# E3-LED_1_3.net
KiCad netlist of a schematic drawn in EAGLE
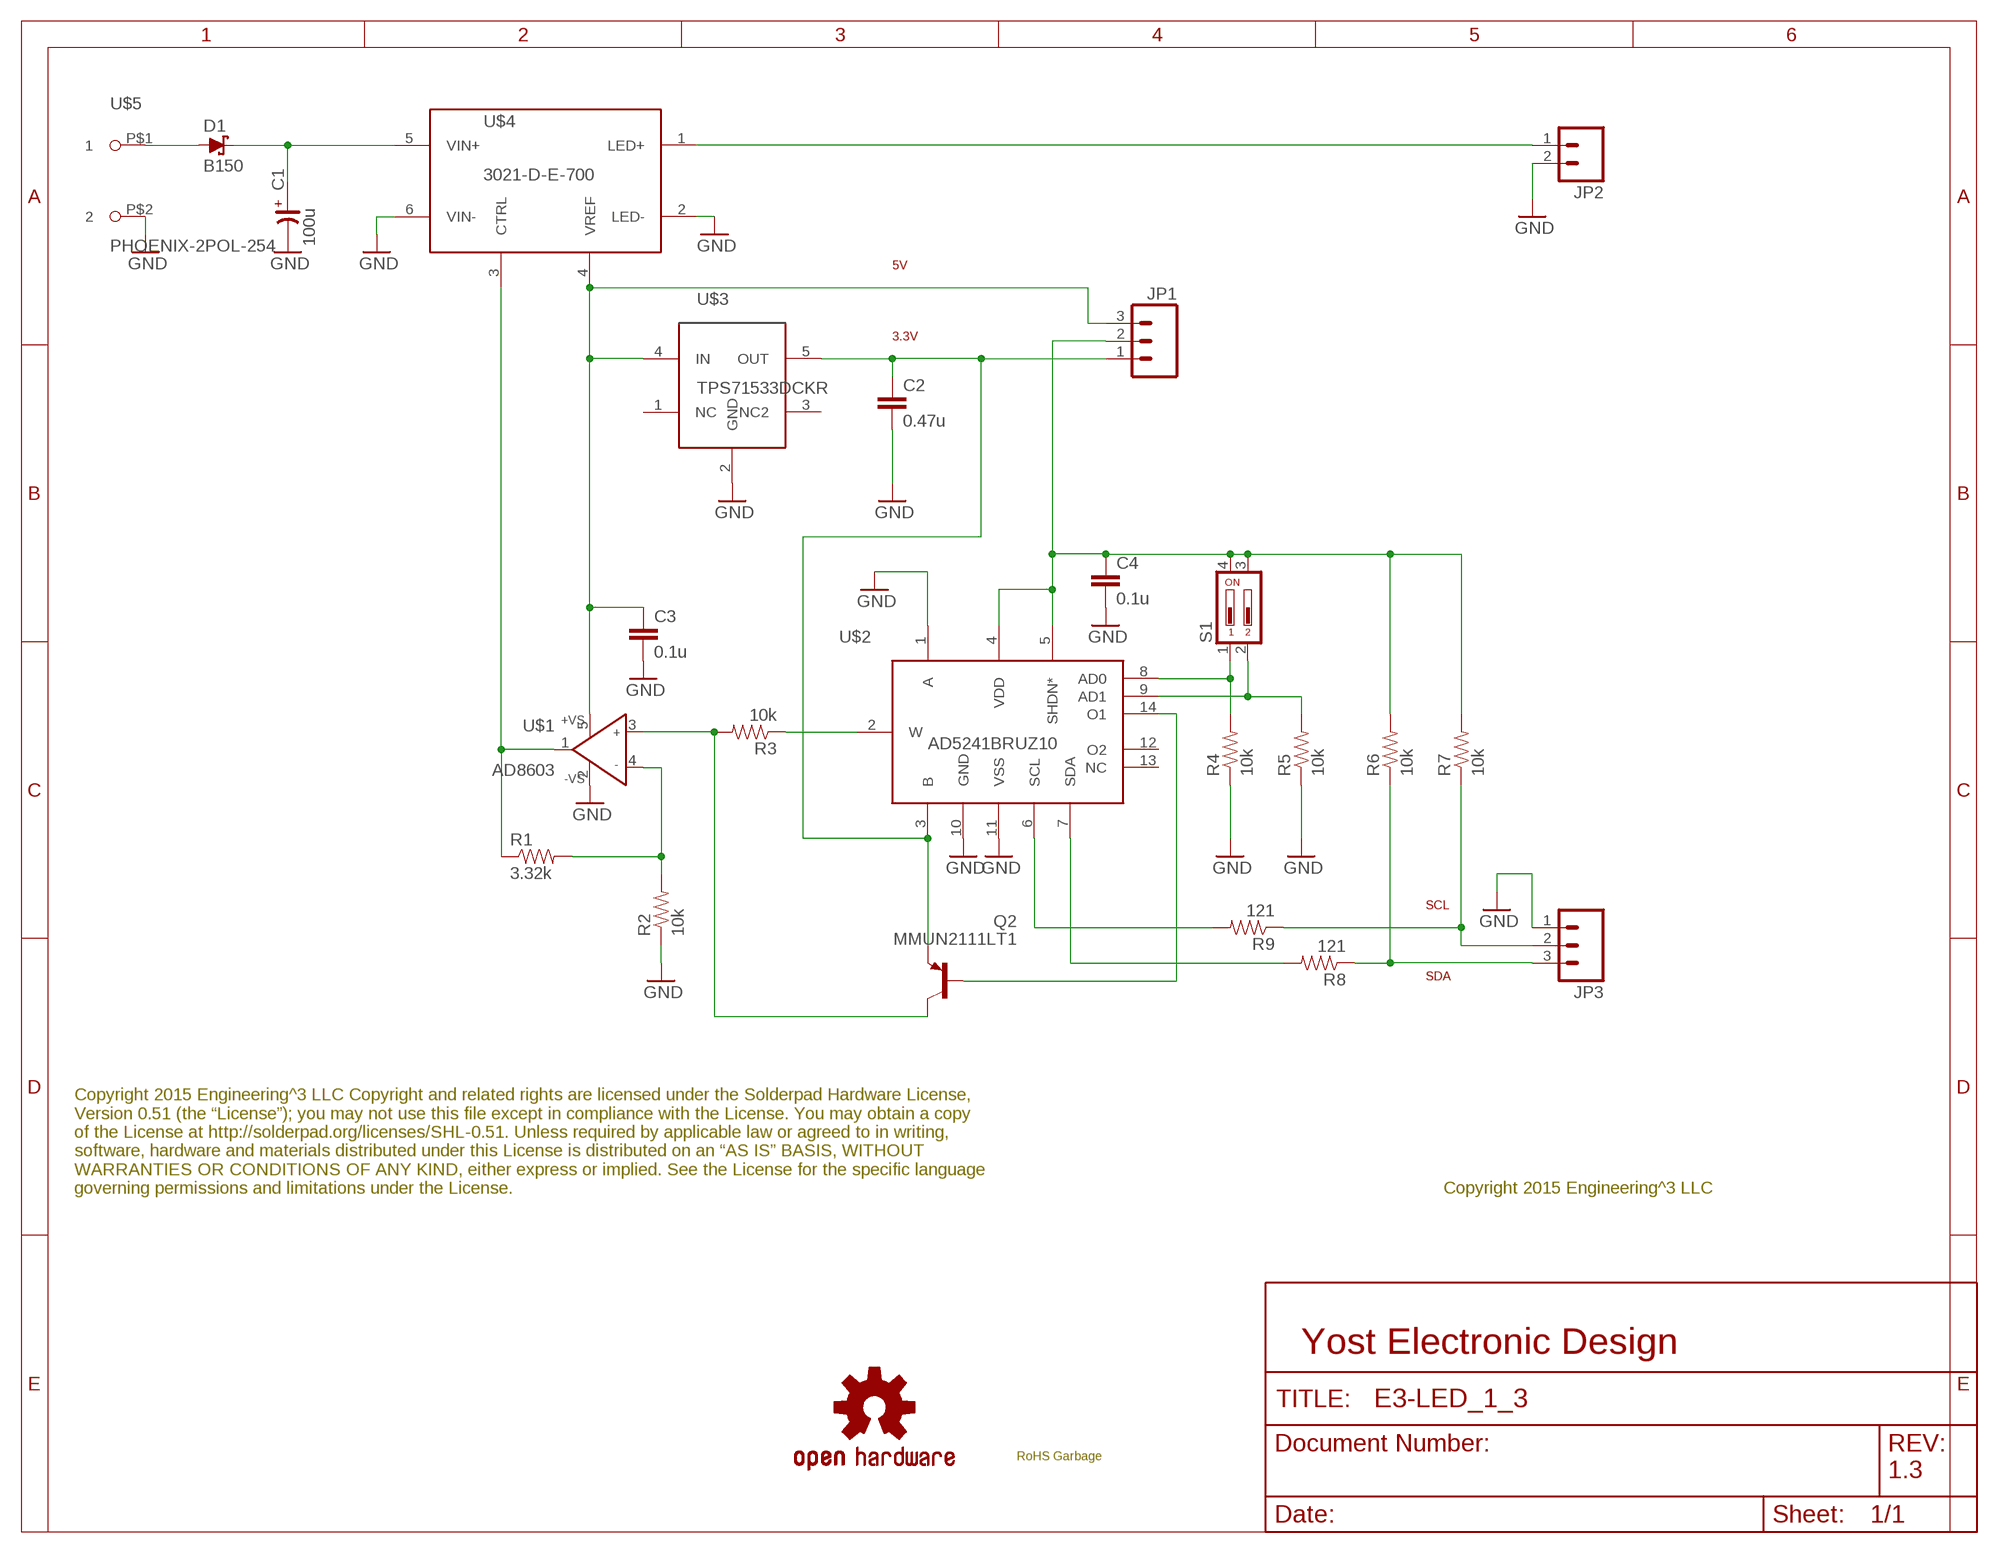
[diagram p0: schematic, sheet 1]

(export (version "E")
  (design (tool "Eeschema 10.0.6"))
  (components
    (comp (ref "C1")
      (value "100u")
      (footprint "eagle-import:SV-E_F")
      (libsource (lib "eagle-import") (part "C-PR-SMD-SV-E/F"))
    )
    (comp (ref "C2")
      (value "0.47u")
      (footprint "eagle-import:0805")
      (libsource (lib "eagle-import") (part "CAP0805"))
    )
    (comp (ref "C3")
      (value "0.1u")
      (footprint "eagle-import:0805")
      (libsource (lib "eagle-import") (part "CAP0805"))
    )
    (comp (ref "C4")
      (value "0.1u")
      (footprint "eagle-import:0805")
      (libsource (lib "eagle-import") (part "CAP0805"))
    )
    (comp (ref "D1")
      (value "B150")
      (footprint "eagle-import:SMB")
      (libsource (lib "eagle-import") (part "SCHOTTKY-DIODESMB"))
    )
    (comp (ref "JP1")
      (value "M03PTH")
      (footprint "eagle-import:1X03")
      (libsource (lib "eagle-import") (part "M03PTH"))
    )
    (comp (ref "JP2")
      (value "M02PTH")
      (footprint "eagle-import:1X02")
      (libsource (lib "eagle-import") (part "M02PTH"))
    )
    (comp (ref "JP3")
      (value "M03PTH")
      (footprint "eagle-import:1X03")
      (libsource (lib "eagle-import") (part "M03PTH"))
    )
    (comp (ref "LOGO1")
      (value "OSHW-LOGOM")
      (footprint "eagle-import:OSHW-LOGO-M")
      (libsource (lib "eagle-import") (part "OSHW-LOGOM"))
    )
    (comp (ref "Q2")
      (value "MMUN2111LT1")
      (footprint "eagle-import:SC59-BEC")
      (libsource (lib "eagle-import") (part "MMUN2111LT1"))
    )
    (comp (ref "R1")
      (value "3.32k")
      (footprint "eagle-import:0805")
      (libsource (lib "eagle-import") (part "RESISTOR"))
    )
    (comp (ref "R2")
      (value "10k")
      (footprint "eagle-import:0805")
      (libsource (lib "eagle-import") (part "RESISTOR"))
    )
    (comp (ref "R3")
      (value "10k")
      (footprint "eagle-import:0805")
      (libsource (lib "eagle-import") (part "RESISTOR"))
    )
    (comp (ref "R4")
      (value "10k")
      (footprint "eagle-import:0805")
      (libsource (lib "eagle-import") (part "RESISTOR"))
    )
    (comp (ref "R5")
      (value "10k")
      (footprint "eagle-import:0805")
      (libsource (lib "eagle-import") (part "RESISTOR"))
    )
    (comp (ref "R6")
      (value "10k")
      (footprint "eagle-import:0805")
      (libsource (lib "eagle-import") (part "RESISTOR"))
    )
    (comp (ref "R7")
      (value "10k")
      (footprint "eagle-import:0805")
      (libsource (lib "eagle-import") (part "RESISTOR"))
    )
    (comp (ref "R8")
      (value "121")
      (footprint "eagle-import:0805")
      (libsource (lib "eagle-import") (part "RESISTOR"))
    )
    (comp (ref "R9")
      (value "121")
      (footprint "eagle-import:0805")
      (libsource (lib "eagle-import") (part "RESISTOR"))
    )
    (comp (ref "S1")
      (value "SD4-02")
      (footprint "eagle-import:SD4-02")
      (libsource (lib "eagle-import") (part "SD4-02"))
    )
    (comp (ref "U$1")
      (value "AD8603")
      (footprint "eagle-import:SOT23-5")
      (libsource (lib "eagle-import") (part "AD8603"))
    )
    (comp (ref "U$2")
      (value "AD5241BRUZ10")
      (footprint "eagle-import:TSOT14")
      (libsource (lib "eagle-import") (part "AD5241BRUZ10"))
    )
    (comp (ref "U$3")
      (value "TPS71533DCKR")
      (footprint "eagle-import:SC70-5")
      (libsource (lib "eagle-import") (part "TPS71533DCKR"))
    )
    (comp (ref "U$4")
      (value "3021-D-E-700")
      (footprint "eagle-import:3021-D-E-700")
      (libsource (lib "eagle-import") (part "3021-D-E-700"))
    )
    (comp (ref "U$5")
      (value "PHOENIX-2POL-254")
      (footprint "eagle-import:2-POL-254")
      (libsource (lib "eagle-import") (part "PHOENIX-2POL-254"))
    )
    (comp (ref "U$6")
      (value "ROHS_GARBAGE")
      (footprint "eagle-import:ROHS_GARBAGE_5MM")
      (libsource (lib "eagle-import") (part "ROHS_GARBAGE"))
    )
  )
  (nets
    (net (code "1") (name "GND") (class "Default")
      (node (ref "C1") (pin "-") (pinfunction "-_-") (pintype "passive"))
      (node (ref "C2") (pin "2") (pinfunction "2_2") (pintype "passive"))
      (node (ref "C3") (pin "2") (pinfunction "2_2") (pintype "passive"))
      (node (ref "C4") (pin "2") (pinfunction "2_2") (pintype "passive"))
      (node (ref "JP2") (pin "2") (pinfunction "2_2") (pintype "passive"))
      (node (ref "JP3") (pin "1") (pinfunction "1_1") (pintype "passive"))
      (node (ref "R2") (pin "1") (pinfunction "1_1") (pintype "passive"))
      (node (ref "R4") (pin "1") (pinfunction "1_1") (pintype "passive"))
      (node (ref "R5") (pin "1") (pinfunction "1_1") (pintype "passive"))
      (node (ref "U$1") (pin "2") (pinfunction "-VS_2") (pintype "input"))
      (node (ref "U$2") (pin "1") (pinfunction "A_1") (pintype "bidirectional"))
      (node (ref "U$2") (pin "10") (pinfunction "GND_10") (pintype "power_in"))
      (node (ref "U$2") (pin "11") (pinfunction "VSS_11") (pintype "power_in"))
      (node (ref "U$3") (pin "2") (pinfunction "GND_2") (pintype "power_in"))
      (node (ref "U$4") (pin "2") (pinfunction "LED-_2") (pintype "power_in"))
      (node (ref "U$4") (pin "6") (pinfunction "VIN-_6") (pintype "power_in"))
      (node (ref "U$5") (pin "P$2") (pinfunction "2_P$2") (pintype "power_in"))
    )
    (net (code "2") (name "Net-(JP3-Pad2)") (class "Default")
      (node (ref "JP3") (pin "2") (pinfunction "2_2") (pintype "passive"))
      (node (ref "R7") (pin "1") (pinfunction "1_1") (pintype "passive"))
      (node (ref "R9") (pin "1") (pinfunction "1_1") (pintype "passive"))
    )
    (net (code "3") (name "Net-(JP3-Pad3)") (class "Default")
      (node (ref "JP3") (pin "3") (pinfunction "3_3") (pintype "passive"))
      (node (ref "R6") (pin "1") (pinfunction "1_1") (pintype "passive"))
      (node (ref "R8") (pin "1") (pinfunction "1_1") (pintype "passive"))
    )
    (net (code "4") (name "Net-(U$1-+VS)") (class "Default")
      (node (ref "C3") (pin "1") (pinfunction "1_1") (pintype "passive"))
      (node (ref "JP1") (pin "3") (pinfunction "3_3") (pintype "passive"))
      (node (ref "U$1") (pin "5") (pinfunction "+VS_5") (pintype "input"))
      (node (ref "U$3") (pin "4") (pinfunction "IN_4") (pintype "power_in"))
      (node (ref "U$4") (pin "4") (pinfunction "VREF_4") (pintype "output"))
    )
    (net (code "5") (name "Net-(U$1-IN-)") (class "Default")
      (node (ref "R1") (pin "2") (pinfunction "2_2") (pintype "passive"))
      (node (ref "R2") (pin "2") (pinfunction "2_2") (pintype "passive"))
      (node (ref "U$1") (pin "4") (pinfunction "IN-_4") (pintype "input"))
    )
    (net (code "6") (name "Net-(U$1-NUMBER)") (class "Default")
      (node (ref "Q2") (pin "C") (pinfunction "C_C") (pintype "passive"))
      (node (ref "R3") (pin "2") (pinfunction "2_2") (pintype "passive"))
      (node (ref "U$1") (pin "3") (pinfunction "NUMBER_3") (pintype "input"))
    )
    (net (code "7") (name "Net-(U$1-OUT)") (class "Default")
      (node (ref "R1") (pin "1") (pinfunction "1_1") (pintype "passive"))
      (node (ref "U$1") (pin "1") (pinfunction "OUT_1") (pintype "output"))
      (node (ref "U$4") (pin "3") (pinfunction "CTRL_3") (pintype "input"))
    )
    (net (code "8") (name "Net-(U$2-AD0)") (class "Default")
      (node (ref "R4") (pin "2") (pinfunction "2_2") (pintype "passive"))
      (node (ref "S1") (pin "1") (pinfunction "1_1") (pintype "passive"))
      (node (ref "U$2") (pin "8") (pinfunction "AD0_8") (pintype "bidirectional"))
    )
    (net (code "9") (name "Net-(U$2-AD1)") (class "Default")
      (node (ref "R5") (pin "2") (pinfunction "2_2") (pintype "passive"))
      (node (ref "S1") (pin "2") (pinfunction "2_2") (pintype "passive"))
      (node (ref "U$2") (pin "9") (pinfunction "AD1_9") (pintype "bidirectional"))
    )
    (net (code "10") (name "Net-(U$2-B)") (class "Default")
      (node (ref "C2") (pin "1") (pinfunction "1_1") (pintype "passive"))
      (node (ref "JP1") (pin "1") (pinfunction "1_1") (pintype "passive"))
      (node (ref "Q2") (pin "E") (pinfunction "E_E") (pintype "passive"))
      (node (ref "U$2") (pin "3") (pinfunction "B_3") (pintype "bidirectional"))
      (node (ref "U$3") (pin "5") (pinfunction "OUT_5") (pintype "power_in"))
    )
    (net (code "11") (name "Net-(U$2-O1)") (class "Default")
      (node (ref "Q2") (pin "B") (pinfunction "B_B") (pintype "passive"))
      (node (ref "U$2") (pin "14") (pinfunction "O1_14") (pintype "bidirectional"))
    )
    (net (code "12") (name "Net-(U$2-SCL)") (class "Default")
      (node (ref "R9") (pin "2") (pinfunction "2_2") (pintype "passive"))
      (node (ref "U$2") (pin "6") (pinfunction "SCL_6") (pintype "bidirectional"))
    )
    (net (code "13") (name "Net-(U$2-SDA)") (class "Default")
      (node (ref "R8") (pin "2") (pinfunction "2_2") (pintype "passive"))
      (node (ref "U$2") (pin "7") (pinfunction "SDA_7") (pintype "bidirectional"))
    )
    (net (code "14") (name "Net-(U$2-SHDN*)") (class "Default")
      (node (ref "C4") (pin "1") (pinfunction "1_1") (pintype "passive"))
      (node (ref "JP1") (pin "2") (pinfunction "2_2") (pintype "passive"))
      (node (ref "R6") (pin "2") (pinfunction "2_2") (pintype "passive"))
      (node (ref "R7") (pin "2") (pinfunction "2_2") (pintype "passive"))
      (node (ref "S1") (pin "3") (pinfunction "3_3") (pintype "passive"))
      (node (ref "S1") (pin "4") (pinfunction "4_4") (pintype "passive"))
      (node (ref "U$2") (pin "4") (pinfunction "VDD_4") (pintype "power_in"))
      (node (ref "U$2") (pin "5") (pinfunction "SHDN*_5") (pintype "bidirectional"))
    )
    (net (code "15") (name "Net-(U$2-W)") (class "Default")
      (node (ref "R3") (pin "1") (pinfunction "1_1") (pintype "passive"))
      (node (ref "U$2") (pin "2") (pinfunction "W_2") (pintype "bidirectional"))
    )
    (net (code "16") (name "Net-(U$4-LED+)") (class "Default")
      (node (ref "JP2") (pin "1") (pinfunction "1_1") (pintype "passive"))
      (node (ref "U$4") (pin "1") (pinfunction "LED+_1") (pintype "output"))
    )
    (net (code "17") (name "Net-(U$4-VIN+)") (class "Default")
      (node (ref "C1") (pin "+") (pinfunction "+_+") (pintype "passive"))
      (node (ref "D1") (pin "C") (pinfunction "C_C") (pintype "passive"))
      (node (ref "U$4") (pin "5") (pinfunction "VIN+_5") (pintype "power_in"))
    )
    (net (code "18") (name "Net-(U$5-1)") (class "Default")
      (node (ref "D1") (pin "A") (pinfunction "A_A") (pintype "passive"))
      (node (ref "U$5") (pin "P$1") (pinfunction "1_P$1") (pintype "power_in"))
    )
    (net (code "19") (name "unconnected-(U$2-NC-Pad13)") (class "Default")
      (node (ref "U$2") (pin "13") (pinfunction "NC_13") (pintype "bidirectional"))
    )
    (net (code "20") (name "unconnected-(U$2-O2-Pad12)") (class "Default")
      (node (ref "U$2") (pin "12") (pinfunction "O2_12") (pintype "bidirectional"))
    )
    (net (code "21") (name "unconnected-(U$3-NC-Pad1)") (class "Default")
      (node (ref "U$3") (pin "1") (pinfunction "NC_1") (pintype "bidirectional"))
    )
    (net (code "22") (name "unconnected-(U$3-NC2-Pad3)") (class "Default")
      (node (ref "U$3") (pin "3") (pinfunction "NC2_3") (pintype "bidirectional"))
    )
  )
)
